# Sheet_1_2023-02-04.net
KiCad netlist of a schematic drawn in Altium Designer
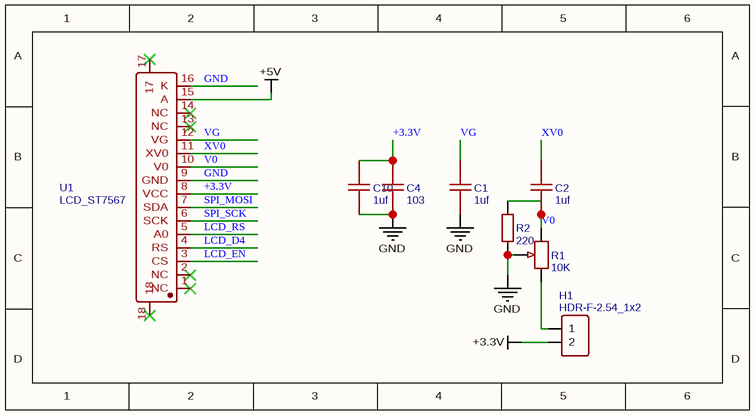
[diagram p0: Sheet_1_2023-02-04.schdoc]

(export (version "E")
  (design (tool "Eeschema 10.0.6"))
  (components
    (comp (ref "C1")
      (value "1uf")
      (fields
        (field (name "BOM_MANUFACTURER PART") "CL21A226MQQNNNE")
        (field (name "BOM_SUPPLIER PART") "C5674")
      )
      (libsource (lib "altium-import") (part "root_1_1uf_"))
    )
    (comp (ref "C2")
      (value "1uf")
      (fields
        (field (name "BOM_MANUFACTURER PART") "CL21A226MQQNNNE")
        (field (name "BOM_SUPPLIER PART") "C5674")
      )
      (libsource (lib "altium-import") (part "root_1_1uf_"))
    )
    (comp (ref "C4")
      (value "103")
      (fields
        (field (name "BOM_MANUFACTURER PART") "CL21A226MQQNNNE")
        (field (name "BOM_SUPPLIER PART") "C5674")
      )
      (libsource (lib "altium-import") (part "root_1_103_"))
    )
    (comp (ref "C10")
      (value "1uf")
      (fields
        (field (name "BOM_MANUFACTURER PART") "CL21A226MQQNNNE")
        (field (name "BOM_SUPPLIER PART") "C5674")
      )
      (libsource (lib "altium-import") (part "root_1_1uf_"))
    )
    (comp (ref "H1")
      (value "HDR-F-2.54_1x2")
      (fields (field (name "BOM_SUPPLIER PART") "C49661") (field (name "CONTRIBUTOR") "Oleg19685"))
      (libsource (lib "altium-import") (part "root_0_HDR-F-2.54_1x2_"))
    )
    (comp (ref "R1")
      (value "10K")
      (fields
        (field (name "BOM_MANUFACTURER PART") "RM063-103 10K")
        (field (name "BOM_SUPPLIER PART") "C38793")
      )
      (libsource (lib "altium-import") (part "root_0_10K_"))
    )
    (comp (ref "R2")
      (value "220")
      (fields
        (field (name "BOM_MANUFACTURER PART") "0805W8F1002T5E")
        (field (name "BOM_SUPPLIER PART") "C17414")
      )
      (libsource (lib "altium-import") (part "root_3_220_"))
    )
    (comp (ref "U1")
      (value "LCD_ST7567")
      (fields (field (name "CONTRIBUTOR") "tung3108vn"))
      (libsource (lib "altium-import") (part "root_0_LCD_ST7567_"))
    )
  )
  (nets
    (net (code "1") (name "+3.3V") (class "Default")
      (node (ref "C10") (pin "2") (pinfunction "2_2") (pintype "passive"))
      (node (ref "C4") (pin "2") (pinfunction "2_2") (pintype "passive"))
      (node (ref "H1") (pin "2") (pinfunction "2_2") (pintype "passive"))
      (node (ref "U1") (pin "8") (pinfunction "VCC_8") (pintype "passive"))
    )
    (net (code "2") (name "+5V") (class "Default")
      (node (ref "U1") (pin "15") (pinfunction "A_15") (pintype "passive"))
    )
    (net (code "3") (name "/LCD_D4") (class "Default")
      (node (ref "U1") (pin "4") (pinfunction "RS_4") (pintype "passive"))
    )
    (net (code "4") (name "/LCD_EN") (class "Default")
      (node (ref "U1") (pin "3") (pinfunction "CS_3") (pintype "passive"))
    )
    (net (code "5") (name "/LCD_RS") (class "Default")
      (node (ref "U1") (pin "5") (pinfunction "A0_5") (pintype "passive"))
    )
    (net (code "6") (name "/SPI_MOSI") (class "Default")
      (node (ref "U1") (pin "7") (pinfunction "SDA_7") (pintype "passive"))
    )
    (net (code "7") (name "/SPI_SCK") (class "Default")
      (node (ref "U1") (pin "6") (pinfunction "SCK_6") (pintype "passive"))
    )
    (net (code "8") (name "/V0") (class "Default")
      (node (ref "C2") (pin "1") (pinfunction "1_1") (pintype "passive"))
      (node (ref "R1") (pin "3") (pinfunction "3_3") (pintype "passive"))
      (node (ref "R2") (pin "1") (pinfunction "1_1") (pintype "passive"))
      (node (ref "U1") (pin "10") (pinfunction "V0_10") (pintype "passive"))
    )
    (net (code "9") (name "/VG") (class "Default")
      (node (ref "C1") (pin "2") (pinfunction "2_2") (pintype "passive"))
      (node (ref "U1") (pin "12") (pinfunction "VG_12") (pintype "passive"))
    )
    (net (code "10") (name "/XV0") (class "Default")
      (node (ref "C2") (pin "2") (pinfunction "2_2") (pintype "passive"))
      (node (ref "U1") (pin "11") (pinfunction "XV0_11") (pintype "passive"))
    )
    (net (code "11") (name "GND") (class "Default")
      (node (ref "C1") (pin "1") (pinfunction "1_1") (pintype "passive"))
      (node (ref "C10") (pin "1") (pinfunction "1_1") (pintype "passive"))
      (node (ref "C4") (pin "1") (pinfunction "1_1") (pintype "passive"))
      (node (ref "R1") (pin "2") (pinfunction "2_2") (pintype "passive"))
      (node (ref "R2") (pin "2") (pinfunction "2_2") (pintype "passive"))
      (node (ref "U1") (pin "16") (pinfunction "K_16") (pintype "passive"))
      (node (ref "U1") (pin "9") (pinfunction "GND_9") (pintype "passive"))
    )
    (net (code "12") (name "Net-(H1-Pad1)") (class "Default")
      (node (ref "H1") (pin "1") (pinfunction "1_1") (pintype "passive"))
      (node (ref "R1") (pin "1") (pinfunction "1_1") (pintype "passive"))
    )
    (net (code "13") (name "unconnected-(U1-NC-Pad1)") (class "Default")
      (node (ref "U1") (pin "1") (pinfunction "NC_1") (pintype "passive+no_connect"))
    )
    (net (code "14") (name "unconnected-(U1-NC-Pad2)") (class "Default")
      (node (ref "U1") (pin "2") (pinfunction "NC_2") (pintype "passive+no_connect"))
    )
    (net (code "15") (name "unconnected-(U1-NC-Pad13)") (class "Default")
      (node (ref "U1") (pin "13") (pinfunction "NC_13") (pintype "passive+no_connect"))
    )
    (net (code "16") (name "unconnected-(U1-NC-Pad14)") (class "Default")
      (node (ref "U1") (pin "14") (pinfunction "NC_14") (pintype "passive+no_connect"))
    )
    (net (code "17") (name "unconnected-(U1-Pad17)") (class "Default")
      (node (ref "U1") (pin "17") (pinfunction "17_17") (pintype "passive+no_connect"))
    )
    (net (code "18") (name "unconnected-(U1-Pad18)") (class "Default")
      (node (ref "U1") (pin "18") (pinfunction "18_18") (pintype "passive+no_connect"))
    )
  )
)
